# part1.net
KiCad netlist of a schematic drawn in Altium Designer
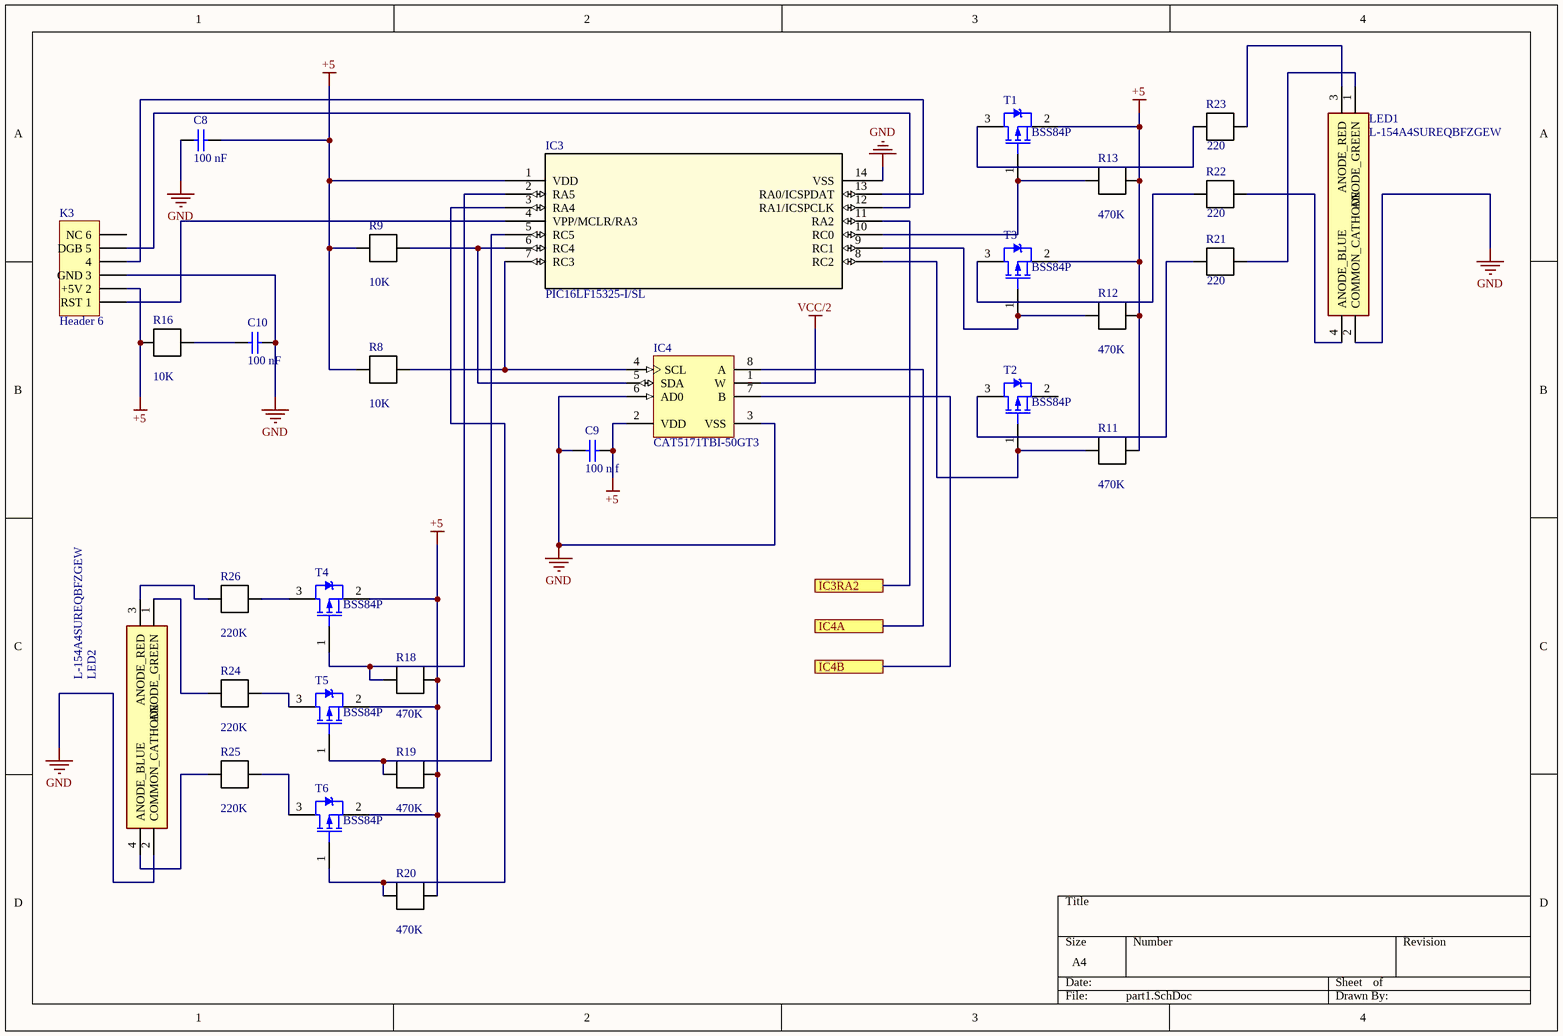
[diagram p0: part1.SchDoc]

(export (version "E")
  (design (tool "Eeschema 10.0.6"))
  (components
    (comp (ref "C8")
      (value "100 nF")
      (footprint "CAPC2013X70X45NL10T25")
      (fields (field (name "MANUFACTURER") "Murata") (field (name "PART NUMBER") "GRM2165C1H332JA01D"))
      (libsource (lib "Altium Content Vault") (part "CAP"))
    )
    (comp (ref "C9")
      (value "100 n f")
      (footprint "CAPC2013X70X45NL10T25")
      (fields (field (name "MANUFACTURER") "Murata") (field (name "PART NUMBER") "GRM2165C1H332JA01D"))
      (libsource (lib "Altium Content Vault") (part "CAP"))
    )
    (comp (ref "C10")
      (value "100 nF")
      (footprint "CAPC2013X70X45NL10T25")
      (fields (field (name "MANUFACTURER") "Murata") (field (name "PART NUMBER") "GRM2165C1H332JA01D"))
      (libsource (lib "Altium Content Vault") (part "CAP"))
    )
    (comp (ref "IC3")
      (value "PIC16LF15325-I/SL")
      (footprint "SOIC14_SL_MCH")
      (description "No Description Available")
      (fields (field (name "COPYRIGHT") "Copyright (C) 2018 Accelerated Designs. All rights reserved"))
      (libsource (lib "2021-03-03_10-40-38") (part "PIC16LF15325-I/SL"))
    )
    (comp (ref "IC4")
      (value "CAT5171TBI-50GT3")
      (footprint "ONSC-SOT23-8-527AK-01_N")
      (fields (field (name "MANUFACTURER") "On Semiconductor"))
      (libsource (lib "Altium Content Vault") (part "ONSC-CAT5171-SOT23-8-527AK-01"))
    )
    (comp (ref "K3")
      (value "Header 6")
      (footprint "HDR1X6")
      (description "Header, 6-Pin")
      (fields (field (name "PUBLISHER") "Altium Limited"))
      (libsource (lib "Miscellaneous Connectors") (part "Header 6"))
    )
    (comp (ref "LED1")
      (value "L-154A4SUREQBFZGEW")
      (footprint "SamacSys:L-154A4SUREQBFZGEC")
      (description "LED")
      (libsource (lib "SamacSys") (part "L-154A4SUREQBFZGEW"))
    )
    (comp (ref "LED2")
      (value "L-154A4SUREQBFZGEW")
      (footprint "SamacSys:L-154A4SUREQBFZGEC")
      (description "LED")
      (libsource (lib "SamacSys") (part "L-154A4SUREQBFZGEW"))
    )
    (comp (ref "R8")
      (value "10K")
      (footprint "6-0805_M")
      (description "Resistor")
      (fields (field (name "PUBLISHER") "Altium Limited"))
      (libsource (lib "bio_lamp") (part "Res1"))
    )
    (comp (ref "R9")
      (value "10K")
      (footprint "6-0805_M")
      (description "Resistor")
      (fields (field (name "PUBLISHER") "Altium Limited"))
      (libsource (lib "bio_lamp") (part "Res1"))
    )
    (comp (ref "R11")
      (value "470K")
      (footprint "C1206")
      (description "Resistor")
      (fields (field (name "PUBLISHER") "Altium Limited"))
      (libsource (lib "bio_lamp") (part "Res1"))
    )
    (comp (ref "R12")
      (value "470K")
      (footprint "C1206")
      (description "Resistor")
      (fields (field (name "PUBLISHER") "Altium Limited"))
      (libsource (lib "bio_lamp") (part "Res1"))
    )
    (comp (ref "R13")
      (value "470K")
      (footprint "C1206")
      (description "Resistor")
      (fields (field (name "PUBLISHER") "Altium Limited"))
      (libsource (lib "bio_lamp") (part "Res1"))
    )
    (comp (ref "R16")
      (value "10K")
      (footprint "6-0805_M")
      (description "Resistor")
      (fields (field (name "PUBLISHER") "Altium Limited"))
      (libsource (lib "bio_lamp") (part "Res1"))
    )
    (comp (ref "R18")
      (value "470K")
      (footprint "C1206")
      (description "Resistor")
      (fields (field (name "PUBLISHER") "Altium Limited"))
      (libsource (lib "bio_lamp") (part "Res1"))
    )
    (comp (ref "R19")
      (value "470K")
      (footprint "C1206")
      (description "Resistor")
      (fields (field (name "PUBLISHER") "Altium Limited"))
      (libsource (lib "bio_lamp") (part "Res1"))
    )
    (comp (ref "R20")
      (value "470K")
      (footprint "C1206")
      (description "Resistor")
      (fields (field (name "PUBLISHER") "Altium Limited"))
      (libsource (lib "bio_lamp") (part "Res1"))
    )
    (comp (ref "R21")
      (value "220")
      (footprint "C1206")
      (description "Resistor")
      (fields (field (name "PUBLISHER") "Altium Limited"))
      (libsource (lib "bio_lamp") (part "Res1"))
    )
    (comp (ref "R22")
      (value "220")
      (footprint "C1206")
      (description "Resistor")
      (fields (field (name "PUBLISHER") "Altium Limited"))
      (libsource (lib "bio_lamp") (part "Res1"))
    )
    (comp (ref "R23")
      (value "220")
      (footprint "C1206")
      (description "Resistor")
      (fields (field (name "PUBLISHER") "Altium Limited"))
      (libsource (lib "bio_lamp") (part "Res1"))
    )
    (comp (ref "R24")
      (value "220K")
      (footprint "C1206")
      (description "Resistor")
      (fields (field (name "PUBLISHER") "Altium Limited"))
      (libsource (lib "bio_lamp") (part "Res1"))
    )
    (comp (ref "R25")
      (value "220K")
      (footprint "C1206")
      (description "Resistor")
      (fields (field (name "PUBLISHER") "Altium Limited"))
      (libsource (lib "bio_lamp") (part "Res1"))
    )
    (comp (ref "R26")
      (value "220K")
      (footprint "C1206")
      (description "Resistor")
      (fields (field (name "PUBLISHER") "Altium Limited"))
      (libsource (lib "bio_lamp") (part "Res1"))
    )
    (comp (ref "T1")
      (value "BSS84P")
      (footprint "INF-PG-SOT23_N")
      (fields (field (name "MANUFACTURER") "Infineon"))
      (libsource (lib "Altium Content Vault") (part "INF-PEMOS-GSD-3-B"))
    )
    (comp (ref "T2")
      (value "BSS84P")
      (footprint "INF-PG-SOT23_N")
      (fields (field (name "MANUFACTURER") "Infineon"))
      (libsource (lib "Altium Content Vault") (part "INF-PEMOS-GSD-3-B"))
    )
    (comp (ref "T3")
      (value "BSS84P")
      (footprint "INF-PG-SOT23_N")
      (fields (field (name "MANUFACTURER") "Infineon"))
      (libsource (lib "Altium Content Vault") (part "INF-PEMOS-GSD-3-B"))
    )
    (comp (ref "T4")
      (value "BSS84P")
      (footprint "INF-PG-SOT23_N")
      (fields (field (name "MANUFACTURER") "Infineon"))
      (libsource (lib "Altium Content Vault") (part "INF-PEMOS-GSD-3-B"))
    )
    (comp (ref "T5")
      (value "BSS84P")
      (footprint "INF-PG-SOT23_N")
      (fields (field (name "MANUFACTURER") "Infineon"))
      (libsource (lib "Altium Content Vault") (part "INF-PEMOS-GSD-3-B"))
    )
    (comp (ref "T6")
      (value "BSS84P")
      (footprint "INF-PG-SOT23_N")
      (fields (field (name "MANUFACTURER") "Infineon"))
      (libsource (lib "Altium Content Vault") (part "INF-PEMOS-GSD-3-B"))
    )
  )
  (nets
    (net (code "1") (name "+5") (class "Default")
      (node (ref "C8") (pin "2") (pinfunction "2_2") (pintype "passive"))
      (node (ref "C9") (pin "2") (pinfunction "2_2") (pintype "passive"))
      (node (ref "IC3") (pin "1") (pinfunction "VDD_1") (pintype "power_in"))
      (node (ref "IC4") (pin "2") (pinfunction "VDD_2") (pintype "power_in"))
      (node (ref "K3") (pin "2") (pinfunction "+5V_2_2") (pintype "passive"))
      (node (ref "R11") (pin "2") (pinfunction "2_2") (pintype "passive"))
      (node (ref "R12") (pin "2") (pinfunction "2_2") (pintype "passive"))
      (node (ref "R13") (pin "2") (pinfunction "2_2") (pintype "passive"))
      (node (ref "R16") (pin "1") (pinfunction "1_1") (pintype "passive"))
      (node (ref "R18") (pin "2") (pinfunction "2_2") (pintype "passive"))
      (node (ref "R19") (pin "2") (pinfunction "2_2") (pintype "passive"))
      (node (ref "R20") (pin "2") (pinfunction "2_2") (pintype "passive"))
      (node (ref "R8") (pin "1") (pinfunction "1_1") (pintype "passive"))
      (node (ref "R9") (pin "1") (pinfunction "1_1") (pintype "passive"))
      (node (ref "T1") (pin "2") (pinfunction "SOURCE_2") (pintype "passive"))
      (node (ref "T3") (pin "2") (pinfunction "SOURCE_2") (pintype "passive"))
      (node (ref "T4") (pin "2") (pinfunction "SOURCE_2") (pintype "passive"))
      (node (ref "T5") (pin "2") (pinfunction "SOURCE_2") (pintype "passive"))
      (node (ref "T6") (pin "2") (pinfunction "SOURCE_2") (pintype "passive"))
    )
    (net (code "2") (name "/IC3RA2") (class "Default")
      (node (ref "IC3") (pin "11") (pinfunction "RA2_11") (pintype "bidirectional"))
    )
    (net (code "3") (name "/IC4A") (class "Default")
      (node (ref "IC4") (pin "8") (pinfunction "A_8") (pintype "passive"))
    )
    (net (code "4") (name "/IC4B") (class "Default")
      (node (ref "IC4") (pin "7") (pinfunction "B_7") (pintype "passive"))
    )
    (net (code "5") (name "GND") (class "Default")
      (node (ref "C10") (pin "2") (pinfunction "2_2") (pintype "passive"))
      (node (ref "C8") (pin "1") (pinfunction "1_1") (pintype "passive"))
      (node (ref "C9") (pin "1") (pinfunction "1_1") (pintype "passive"))
      (node (ref "IC3") (pin "14") (pinfunction "VSS_14") (pintype "passive"))
      (node (ref "IC4") (pin "3") (pinfunction "VSS_3") (pintype "power_in"))
      (node (ref "IC4") (pin "6") (pinfunction "AD0_6") (pintype "input"))
      (node (ref "K3") (pin "3") (pinfunction "GND_3_3") (pintype "passive"))
      (node (ref "LED1") (pin "2") (pinfunction "COMMON_CATHODE_2") (pintype "passive"))
      (node (ref "LED2") (pin "2") (pinfunction "COMMON_CATHODE_2") (pintype "passive"))
    )
    (net (code "6") (name "Net-(C10-Pad1)") (class "Default")
      (node (ref "C10") (pin "1") (pinfunction "1_1") (pintype "passive"))
      (node (ref "R16") (pin "2") (pinfunction "2_2") (pintype "passive"))
    )
    (net (code "7") (name "Net-(IC3-RA0{slash}ICSPDAT)") (class "Default")
      (node (ref "IC3") (pin "13") (pinfunction "RA0/ICSPDAT_13") (pintype "bidirectional"))
      (node (ref "K3") (pin "4") (pinfunction "4_4") (pintype "passive"))
    )
    (net (code "8") (name "Net-(IC3-RA1{slash}ICSPCLK)") (class "Default")
      (node (ref "IC3") (pin "12") (pinfunction "RA1/ICSPCLK_12") (pintype "bidirectional"))
      (node (ref "K3") (pin "5") (pinfunction "DGB_5_5") (pintype "passive"))
    )
    (net (code "9") (name "Net-(IC3-RA4)") (class "Default")
      (node (ref "IC3") (pin "3") (pinfunction "RA4_3") (pintype "bidirectional"))
      (node (ref "R20") (pin "1") (pinfunction "1_1") (pintype "passive"))
      (node (ref "T6") (pin "1") (pinfunction "GATE_1") (pintype "passive"))
    )
    (net (code "10") (name "Net-(IC3-RA5)") (class "Default")
      (node (ref "IC3") (pin "2") (pinfunction "RA5_2") (pintype "bidirectional"))
      (node (ref "R18") (pin "1") (pinfunction "1_1") (pintype "passive"))
      (node (ref "T4") (pin "1") (pinfunction "GATE_1") (pintype "passive"))
    )
    (net (code "11") (name "Net-(IC3-RC0)") (class "Default")
      (node (ref "IC3") (pin "10") (pinfunction "RC0_10") (pintype "bidirectional"))
      (node (ref "R13") (pin "1") (pinfunction "1_1") (pintype "passive"))
      (node (ref "T1") (pin "1") (pinfunction "GATE_1") (pintype "passive"))
    )
    (net (code "12") (name "Net-(IC3-RC1)") (class "Default")
      (node (ref "IC3") (pin "9") (pinfunction "RC1_9") (pintype "bidirectional"))
      (node (ref "R12") (pin "1") (pinfunction "1_1") (pintype "passive"))
      (node (ref "T3") (pin "1") (pinfunction "GATE_1") (pintype "passive"))
    )
    (net (code "13") (name "Net-(IC3-RC2)") (class "Default")
      (node (ref "IC3") (pin "8") (pinfunction "RC2_8") (pintype "bidirectional"))
      (node (ref "R11") (pin "1") (pinfunction "1_1") (pintype "passive"))
      (node (ref "T2") (pin "1") (pinfunction "GATE_1") (pintype "passive"))
    )
    (net (code "14") (name "Net-(IC3-RC3)") (class "Default")
      (node (ref "IC3") (pin "7") (pinfunction "RC3_7") (pintype "bidirectional"))
      (node (ref "IC4") (pin "4") (pinfunction "SCL_4") (pintype "input"))
      (node (ref "R8") (pin "2") (pinfunction "2_2") (pintype "passive"))
    )
    (net (code "15") (name "Net-(IC3-RC4)") (class "Default")
      (node (ref "IC3") (pin "6") (pinfunction "RC4_6") (pintype "bidirectional"))
      (node (ref "IC4") (pin "5") (pinfunction "SDA_5") (pintype "bidirectional"))
      (node (ref "R9") (pin "2") (pinfunction "2_2") (pintype "passive"))
    )
    (net (code "16") (name "Net-(IC3-RC5)") (class "Default")
      (node (ref "IC3") (pin "5") (pinfunction "RC5_5") (pintype "bidirectional"))
      (node (ref "R19") (pin "1") (pinfunction "1_1") (pintype "passive"))
      (node (ref "T5") (pin "1") (pinfunction "GATE_1") (pintype "passive"))
    )
    (net (code "17") (name "Net-(IC3-VPP{slash}MCLR{slash}RA3)") (class "Default")
      (node (ref "IC3") (pin "4") (pinfunction "VPP/MCLR/RA3_4") (pintype "power_in"))
      (node (ref "K3") (pin "1") (pinfunction "RST_1_1") (pintype "passive"))
    )
    (net (code "18") (name "Net-(LED1-ANODE_BLUE)") (class "Default")
      (node (ref "LED1") (pin "4") (pinfunction "ANODE_BLUE_4") (pintype "passive"))
      (node (ref "R22") (pin "2") (pinfunction "2_2") (pintype "passive"))
    )
    (net (code "19") (name "Net-(LED1-ANODE_GREEN)") (class "Default")
      (node (ref "LED1") (pin "1") (pinfunction "ANODE_GREEN_1") (pintype "passive"))
      (node (ref "R21") (pin "2") (pinfunction "2_2") (pintype "passive"))
    )
    (net (code "20") (name "Net-(LED1-ANODE_RED)") (class "Default")
      (node (ref "LED1") (pin "3") (pinfunction "ANODE_RED_3") (pintype "passive"))
      (node (ref "R23") (pin "2") (pinfunction "2_2") (pintype "passive"))
    )
    (net (code "21") (name "Net-(LED2-ANODE_BLUE)") (class "Default")
      (node (ref "LED2") (pin "4") (pinfunction "ANODE_BLUE_4") (pintype "passive"))
      (node (ref "R25") (pin "1") (pinfunction "1_1") (pintype "passive"))
    )
    (net (code "22") (name "Net-(LED2-ANODE_GREEN)") (class "Default")
      (node (ref "LED2") (pin "1") (pinfunction "ANODE_GREEN_1") (pintype "passive"))
      (node (ref "R24") (pin "1") (pinfunction "1_1") (pintype "passive"))
    )
    (net (code "23") (name "Net-(LED2-ANODE_RED)") (class "Default")
      (node (ref "LED2") (pin "3") (pinfunction "ANODE_RED_3") (pintype "passive"))
      (node (ref "R26") (pin "1") (pinfunction "1_1") (pintype "passive"))
    )
    (net (code "24") (name "Net-(T1-DRAIN)") (class "Default")
      (node (ref "R23") (pin "1") (pinfunction "1_1") (pintype "passive"))
      (node (ref "T1") (pin "3") (pinfunction "DRAIN_3") (pintype "passive"))
    )
    (net (code "25") (name "Net-(T2-DRAIN)") (class "Default")
      (node (ref "R21") (pin "1") (pinfunction "1_1") (pintype "passive"))
      (node (ref "T2") (pin "3") (pinfunction "DRAIN_3") (pintype "passive"))
    )
    (net (code "26") (name "Net-(T3-DRAIN)") (class "Default")
      (node (ref "R22") (pin "1") (pinfunction "1_1") (pintype "passive"))
      (node (ref "T3") (pin "3") (pinfunction "DRAIN_3") (pintype "passive"))
    )
    (net (code "27") (name "Net-(T4-DRAIN)") (class "Default")
      (node (ref "R26") (pin "2") (pinfunction "2_2") (pintype "passive"))
      (node (ref "T4") (pin "3") (pinfunction "DRAIN_3") (pintype "passive"))
    )
    (net (code "28") (name "Net-(T5-DRAIN)") (class "Default")
      (node (ref "R24") (pin "2") (pinfunction "2_2") (pintype "passive"))
      (node (ref "T5") (pin "3") (pinfunction "DRAIN_3") (pintype "passive"))
    )
    (net (code "29") (name "Net-(T6-DRAIN)") (class "Default")
      (node (ref "R25") (pin "2") (pinfunction "2_2") (pintype "passive"))
      (node (ref "T6") (pin "3") (pinfunction "DRAIN_3") (pintype "passive"))
    )
    (net (code "30") (name "VCC{slash}2") (class "Default")
      (node (ref "IC4") (pin "1") (pinfunction "W_1") (pintype "passive"))
    )
    (net (code "31") (name "unconnected-(K3-NC_6-Pad6)") (class "Default")
      (node (ref "K3") (pin "6") (pinfunction "NC_6_6") (pintype "passive"))
    )
    (net (code "32") (name "unconnected-(T2-SOURCE-Pad2)") (class "Default")
      (node (ref "T2") (pin "2") (pinfunction "SOURCE_2") (pintype "passive"))
    )
  )
)
